# baro.net
KiCad netlist of a schematic drawn in EAGLE
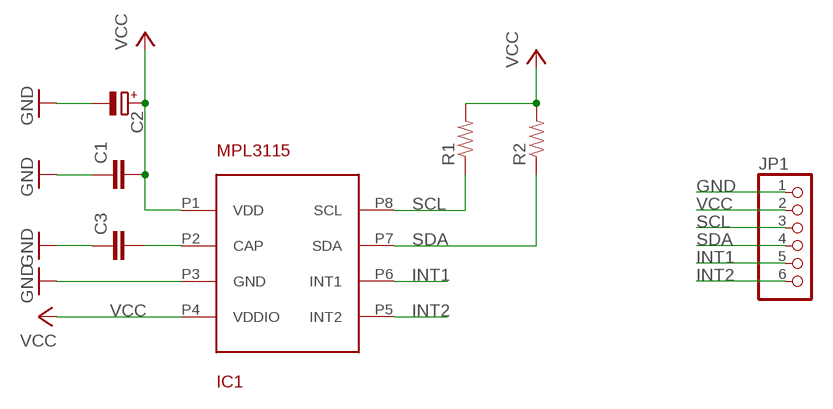
[diagram p0: schematic, sheet 1]

(export (version "E")
  (design (tool "Eeschema 10.0.6"))
  (components
    (comp (ref "C1")
      (value "CAP0805")
      (footprint "eagle-import:0805")
      (libsource (lib "eagle-import") (part "CAP0805"))
    )
    (comp (ref "C2")
      (value "CPOL-EUSMCC")
      (footprint "eagle-import:SMC_C")
      (libsource (lib "eagle-import") (part "CPOL-EUSMCC"))
    )
    (comp (ref "C3")
      (value "CAP0805")
      (footprint "eagle-import:0805")
      (libsource (lib "eagle-import") (part "CAP0805"))
    )
    (comp (ref "IC1")
      (value "MPL3115A2")
      (footprint "eagle-import:LGA8")
      (libsource (lib "eagle-import") (part "MPL3115A2"))
    )
    (comp (ref "JP1")
      (value "PINHD-1X6")
      (footprint "eagle-import:1X06")
      (libsource (lib "eagle-import") (part "PINHD-1X6"))
    )
    (comp (ref "R1")
      (value "RESISTOR0805-RES")
      (footprint "eagle-import:0805")
      (libsource (lib "eagle-import") (part "RESISTOR0805-RES"))
    )
    (comp (ref "R2")
      (value "RESISTOR0805-RES")
      (footprint "eagle-import:0805")
      (libsource (lib "eagle-import") (part "RESISTOR0805-RES"))
    )
  )
  (nets
    (net (code "1") (name "/INT1") (class "Default")
      (node (ref "IC1") (pin "P6") (pinfunction "INT1_P6") (pintype "bidirectional"))
      (node (ref "JP1") (pin "5") (pinfunction "5_5") (pintype "passive"))
    )
    (net (code "2") (name "/INT2") (class "Default")
      (node (ref "IC1") (pin "P5") (pinfunction "INT2_P5") (pintype "bidirectional"))
      (node (ref "JP1") (pin "6") (pinfunction "6_6") (pintype "passive"))
    )
    (net (code "3") (name "/SCL") (class "Default")
      (node (ref "IC1") (pin "P8") (pinfunction "SCL_P8") (pintype "bidirectional"))
      (node (ref "JP1") (pin "3") (pinfunction "3_3") (pintype "passive"))
      (node (ref "R1") (pin "1") (pinfunction "1_1") (pintype "passive"))
    )
    (net (code "4") (name "/SDA") (class "Default")
      (node (ref "IC1") (pin "P7") (pinfunction "SDA_P7") (pintype "bidirectional"))
      (node (ref "JP1") (pin "4") (pinfunction "4_4") (pintype "passive"))
      (node (ref "R2") (pin "1") (pinfunction "1_1") (pintype "passive"))
    )
    (net (code "5") (name "GND") (class "Default")
      (node (ref "C1") (pin "1") (pinfunction "1_1") (pintype "passive"))
      (node (ref "C2") (pin "-") (pinfunction "-_-") (pintype "passive"))
      (node (ref "C3") (pin "1") (pinfunction "1_1") (pintype "passive"))
      (node (ref "IC1") (pin "P3") (pinfunction "GND_P3") (pintype "bidirectional"))
      (node (ref "JP1") (pin "1") (pinfunction "1_1") (pintype "passive"))
    )
    (net (code "6") (name "Net-(IC1-CAP)") (class "Default")
      (node (ref "C3") (pin "2") (pinfunction "2_2") (pintype "passive"))
      (node (ref "IC1") (pin "P2") (pinfunction "CAP_P2") (pintype "bidirectional"))
    )
    (net (code "7") (name "VCC") (class "Default")
      (node (ref "C1") (pin "2") (pinfunction "2_2") (pintype "passive"))
      (node (ref "C2") (pin "+") (pinfunction "+_+") (pintype "passive"))
      (node (ref "IC1") (pin "P1") (pinfunction "VDD_P1") (pintype "bidirectional"))
      (node (ref "IC1") (pin "P4") (pinfunction "VDDIO_P4") (pintype "bidirectional"))
      (node (ref "JP1") (pin "2") (pinfunction "2_2") (pintype "passive"))
      (node (ref "R1") (pin "2") (pinfunction "2_2") (pintype "passive"))
      (node (ref "R2") (pin "2") (pinfunction "2_2") (pintype "passive"))
    )
  )
)
